# button_controller_v1_0.net
KiCad netlist of a schematic drawn in EAGLE
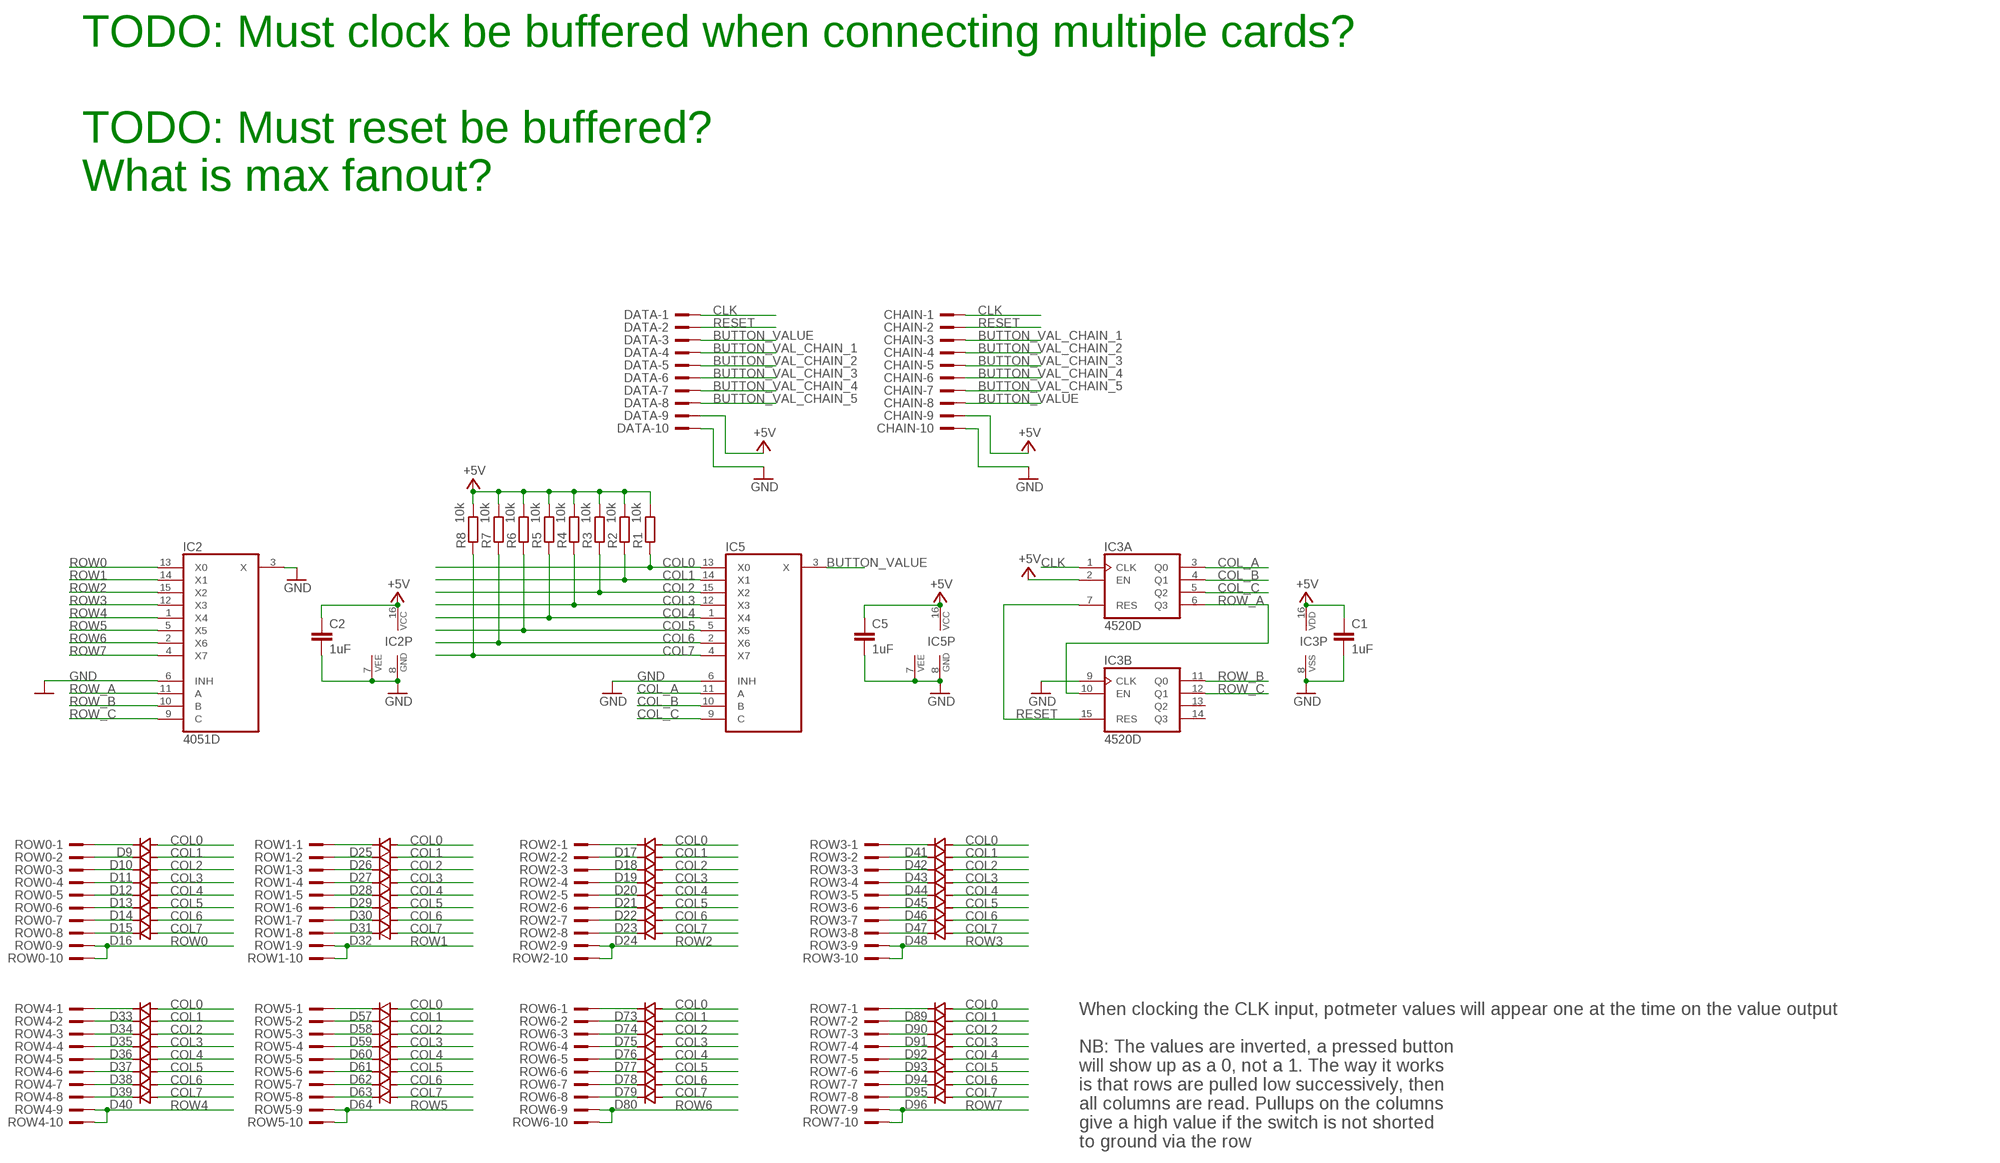
[diagram p0: schematic, sheet 1]

(export (version "E")
  (design (tool "Eeschema 10.0.6"))
  (components
    (comp (ref "C1")
      (value "1uF")
      (footprint "eagle-import:C0603-J")
      (libsource (lib "eagle-import") (part "C-EU-J0603"))
    )
    (comp (ref "C2")
      (value "1uF")
      (footprint "eagle-import:C0603-J")
      (libsource (lib "eagle-import") (part "C-EU-J0603"))
    )
    (comp (ref "C5")
      (value "1uF")
      (footprint "eagle-import:C0603-J")
      (libsource (lib "eagle-import") (part "C-EU-J0603"))
    )
    (comp (ref "CHAIN")
      (value "CONN-IDC-10PS")
      (footprint "eagle-import:CONN-IDC10P-S")
      (libsource (lib "eagle-import") (part "CONN-IDC-10PS"))
    )
    (comp (ref "D9")
      (value "1N4148SOD323")
      (footprint "eagle-import:SOD323J")
      (libsource (lib "eagle-import") (part "1N4148SOD323"))
    )
    (comp (ref "D10")
      (value "1N4148SOD323")
      (footprint "eagle-import:SOD323J")
      (libsource (lib "eagle-import") (part "1N4148SOD323"))
    )
    (comp (ref "D11")
      (value "1N4148SOD323")
      (footprint "eagle-import:SOD323J")
      (libsource (lib "eagle-import") (part "1N4148SOD323"))
    )
    (comp (ref "D12")
      (value "1N4148SOD323")
      (footprint "eagle-import:SOD323J")
      (libsource (lib "eagle-import") (part "1N4148SOD323"))
    )
    (comp (ref "D13")
      (value "1N4148SOD323")
      (footprint "eagle-import:SOD323J")
      (libsource (lib "eagle-import") (part "1N4148SOD323"))
    )
    (comp (ref "D14")
      (value "1N4148SOD323")
      (footprint "eagle-import:SOD323J")
      (libsource (lib "eagle-import") (part "1N4148SOD323"))
    )
    (comp (ref "D15")
      (value "1N4148SOD323")
      (footprint "eagle-import:SOD323J")
      (libsource (lib "eagle-import") (part "1N4148SOD323"))
    )
    (comp (ref "D16")
      (value "1N4148SOD323")
      (footprint "eagle-import:SOD323J")
      (libsource (lib "eagle-import") (part "1N4148SOD323"))
    )
    (comp (ref "D17")
      (value "1N4148SOD323")
      (footprint "eagle-import:SOD323J")
      (libsource (lib "eagle-import") (part "1N4148SOD323"))
    )
    (comp (ref "D18")
      (value "1N4148SOD323")
      (footprint "eagle-import:SOD323J")
      (libsource (lib "eagle-import") (part "1N4148SOD323"))
    )
    (comp (ref "D19")
      (value "1N4148SOD323")
      (footprint "eagle-import:SOD323J")
      (libsource (lib "eagle-import") (part "1N4148SOD323"))
    )
    (comp (ref "D20")
      (value "1N4148SOD323")
      (footprint "eagle-import:SOD323J")
      (libsource (lib "eagle-import") (part "1N4148SOD323"))
    )
    (comp (ref "D21")
      (value "1N4148SOD323")
      (footprint "eagle-import:SOD323J")
      (libsource (lib "eagle-import") (part "1N4148SOD323"))
    )
    (comp (ref "D22")
      (value "1N4148SOD323")
      (footprint "eagle-import:SOD323J")
      (libsource (lib "eagle-import") (part "1N4148SOD323"))
    )
    (comp (ref "D23")
      (value "1N4148SOD323")
      (footprint "eagle-import:SOD323J")
      (libsource (lib "eagle-import") (part "1N4148SOD323"))
    )
    (comp (ref "D24")
      (value "1N4148SOD323")
      (footprint "eagle-import:SOD323J")
      (libsource (lib "eagle-import") (part "1N4148SOD323"))
    )
    (comp (ref "D25")
      (value "1N4148SOD323")
      (footprint "eagle-import:SOD323J")
      (libsource (lib "eagle-import") (part "1N4148SOD323"))
    )
    (comp (ref "D26")
      (value "1N4148SOD323")
      (footprint "eagle-import:SOD323J")
      (libsource (lib "eagle-import") (part "1N4148SOD323"))
    )
    (comp (ref "D27")
      (value "1N4148SOD323")
      (footprint "eagle-import:SOD323J")
      (libsource (lib "eagle-import") (part "1N4148SOD323"))
    )
    (comp (ref "D28")
      (value "1N4148SOD323")
      (footprint "eagle-import:SOD323J")
      (libsource (lib "eagle-import") (part "1N4148SOD323"))
    )
    (comp (ref "D29")
      (value "1N4148SOD323")
      (footprint "eagle-import:SOD323J")
      (libsource (lib "eagle-import") (part "1N4148SOD323"))
    )
    (comp (ref "D30")
      (value "1N4148SOD323")
      (footprint "eagle-import:SOD323J")
      (libsource (lib "eagle-import") (part "1N4148SOD323"))
    )
    (comp (ref "D31")
      (value "1N4148SOD323")
      (footprint "eagle-import:SOD323J")
      (libsource (lib "eagle-import") (part "1N4148SOD323"))
    )
    (comp (ref "D32")
      (value "1N4148SOD323")
      (footprint "eagle-import:SOD323J")
      (libsource (lib "eagle-import") (part "1N4148SOD323"))
    )
    (comp (ref "D33")
      (value "1N4148SOD323")
      (footprint "eagle-import:SOD323J")
      (libsource (lib "eagle-import") (part "1N4148SOD323"))
    )
    (comp (ref "D34")
      (value "1N4148SOD323")
      (footprint "eagle-import:SOD323J")
      (libsource (lib "eagle-import") (part "1N4148SOD323"))
    )
    (comp (ref "D35")
      (value "1N4148SOD323")
      (footprint "eagle-import:SOD323J")
      (libsource (lib "eagle-import") (part "1N4148SOD323"))
    )
    (comp (ref "D36")
      (value "1N4148SOD323")
      (footprint "eagle-import:SOD323J")
      (libsource (lib "eagle-import") (part "1N4148SOD323"))
    )
    (comp (ref "D37")
      (value "1N4148SOD323")
      (footprint "eagle-import:SOD323J")
      (libsource (lib "eagle-import") (part "1N4148SOD323"))
    )
    (comp (ref "D38")
      (value "1N4148SOD323")
      (footprint "eagle-import:SOD323J")
      (libsource (lib "eagle-import") (part "1N4148SOD323"))
    )
    (comp (ref "D39")
      (value "1N4148SOD323")
      (footprint "eagle-import:SOD323J")
      (libsource (lib "eagle-import") (part "1N4148SOD323"))
    )
    (comp (ref "D40")
      (value "1N4148SOD323")
      (footprint "eagle-import:SOD323J")
      (libsource (lib "eagle-import") (part "1N4148SOD323"))
    )
    (comp (ref "D41")
      (value "1N4148SOD323")
      (footprint "eagle-import:SOD323J")
      (libsource (lib "eagle-import") (part "1N4148SOD323"))
    )
    (comp (ref "D42")
      (value "1N4148SOD323")
      (footprint "eagle-import:SOD323J")
      (libsource (lib "eagle-import") (part "1N4148SOD323"))
    )
    (comp (ref "D43")
      (value "1N4148SOD323")
      (footprint "eagle-import:SOD323J")
      (libsource (lib "eagle-import") (part "1N4148SOD323"))
    )
    (comp (ref "D44")
      (value "1N4148SOD323")
      (footprint "eagle-import:SOD323J")
      (libsource (lib "eagle-import") (part "1N4148SOD323"))
    )
    (comp (ref "D45")
      (value "1N4148SOD323")
      (footprint "eagle-import:SOD323J")
      (libsource (lib "eagle-import") (part "1N4148SOD323"))
    )
    (comp (ref "D46")
      (value "1N4148SOD323")
      (footprint "eagle-import:SOD323J")
      (libsource (lib "eagle-import") (part "1N4148SOD323"))
    )
    (comp (ref "D47")
      (value "1N4148SOD323")
      (footprint "eagle-import:SOD323J")
      (libsource (lib "eagle-import") (part "1N4148SOD323"))
    )
    (comp (ref "D48")
      (value "1N4148SOD323")
      (footprint "eagle-import:SOD323J")
      (libsource (lib "eagle-import") (part "1N4148SOD323"))
    )
    (comp (ref "D57")
      (value "1N4148SOD323")
      (footprint "eagle-import:SOD323J")
      (libsource (lib "eagle-import") (part "1N4148SOD323"))
    )
    (comp (ref "D58")
      (value "1N4148SOD323")
      (footprint "eagle-import:SOD323J")
      (libsource (lib "eagle-import") (part "1N4148SOD323"))
    )
    (comp (ref "D59")
      (value "1N4148SOD323")
      (footprint "eagle-import:SOD323J")
      (libsource (lib "eagle-import") (part "1N4148SOD323"))
    )
    (comp (ref "D60")
      (value "1N4148SOD323")
      (footprint "eagle-import:SOD323J")
      (libsource (lib "eagle-import") (part "1N4148SOD323"))
    )
    (comp (ref "D61")
      (value "1N4148SOD323")
      (footprint "eagle-import:SOD323J")
      (libsource (lib "eagle-import") (part "1N4148SOD323"))
    )
    (comp (ref "D62")
      (value "1N4148SOD323")
      (footprint "eagle-import:SOD323J")
      (libsource (lib "eagle-import") (part "1N4148SOD323"))
    )
    (comp (ref "D63")
      (value "1N4148SOD323")
      (footprint "eagle-import:SOD323J")
      (libsource (lib "eagle-import") (part "1N4148SOD323"))
    )
    (comp (ref "D64")
      (value "1N4148SOD323")
      (footprint "eagle-import:SOD323J")
      (libsource (lib "eagle-import") (part "1N4148SOD323"))
    )
    (comp (ref "D73")
      (value "1N4148SOD323")
      (footprint "eagle-import:SOD323J")
      (libsource (lib "eagle-import") (part "1N4148SOD323"))
    )
    (comp (ref "D74")
      (value "1N4148SOD323")
      (footprint "eagle-import:SOD323J")
      (libsource (lib "eagle-import") (part "1N4148SOD323"))
    )
    (comp (ref "D75")
      (value "1N4148SOD323")
      (footprint "eagle-import:SOD323J")
      (libsource (lib "eagle-import") (part "1N4148SOD323"))
    )
    (comp (ref "D76")
      (value "1N4148SOD323")
      (footprint "eagle-import:SOD323J")
      (libsource (lib "eagle-import") (part "1N4148SOD323"))
    )
    (comp (ref "D77")
      (value "1N4148SOD323")
      (footprint "eagle-import:SOD323J")
      (libsource (lib "eagle-import") (part "1N4148SOD323"))
    )
    (comp (ref "D78")
      (value "1N4148SOD323")
      (footprint "eagle-import:SOD323J")
      (libsource (lib "eagle-import") (part "1N4148SOD323"))
    )
    (comp (ref "D79")
      (value "1N4148SOD323")
      (footprint "eagle-import:SOD323J")
      (libsource (lib "eagle-import") (part "1N4148SOD323"))
    )
    (comp (ref "D80")
      (value "1N4148SOD323")
      (footprint "eagle-import:SOD323J")
      (libsource (lib "eagle-import") (part "1N4148SOD323"))
    )
    (comp (ref "D89")
      (value "1N4148SOD323")
      (footprint "eagle-import:SOD323J")
      (libsource (lib "eagle-import") (part "1N4148SOD323"))
    )
    (comp (ref "D90")
      (value "1N4148SOD323")
      (footprint "eagle-import:SOD323J")
      (libsource (lib "eagle-import") (part "1N4148SOD323"))
    )
    (comp (ref "D91")
      (value "1N4148SOD323")
      (footprint "eagle-import:SOD323J")
      (libsource (lib "eagle-import") (part "1N4148SOD323"))
    )
    (comp (ref "D92")
      (value "1N4148SOD323")
      (footprint "eagle-import:SOD323J")
      (libsource (lib "eagle-import") (part "1N4148SOD323"))
    )
    (comp (ref "D93")
      (value "1N4148SOD323")
      (footprint "eagle-import:SOD323J")
      (libsource (lib "eagle-import") (part "1N4148SOD323"))
    )
    (comp (ref "D94")
      (value "1N4148SOD323")
      (footprint "eagle-import:SOD323J")
      (libsource (lib "eagle-import") (part "1N4148SOD323"))
    )
    (comp (ref "D95")
      (value "1N4148SOD323")
      (footprint "eagle-import:SOD323J")
      (libsource (lib "eagle-import") (part "1N4148SOD323"))
    )
    (comp (ref "D96")
      (value "1N4148SOD323")
      (footprint "eagle-import:SOD323J")
      (libsource (lib "eagle-import") (part "1N4148SOD323"))
    )
    (comp (ref "DATA")
      (value "CONN-IDC-10PS")
      (footprint "eagle-import:CONN-IDC10P-S")
      (libsource (lib "eagle-import") (part "CONN-IDC-10PS"))
    )
    (comp (ref "IC2")
      (value "4051D")
      (footprint "eagle-import:SO16")
      (libsource (lib "eagle-import") (part "4051D"))
    )
    (comp (ref "IC3")
      (value "4520D")
      (footprint "eagle-import:SO16")
      (libsource (lib "eagle-import") (part "4520D"))
    )
    (comp (ref "IC5")
      (value "4051D")
      (footprint "eagle-import:SO16")
      (libsource (lib "eagle-import") (part "4051D"))
    )
    (comp (ref "R1")
      (value "10k")
      (footprint "eagle-import:R0603")
      (libsource (lib "eagle-import") (part "R-EU_R0603"))
    )
    (comp (ref "R2")
      (value "10k")
      (footprint "eagle-import:R0603")
      (libsource (lib "eagle-import") (part "R-EU_R0603"))
    )
    (comp (ref "R3")
      (value "10k")
      (footprint "eagle-import:R0603")
      (libsource (lib "eagle-import") (part "R-EU_R0603"))
    )
    (comp (ref "R4")
      (value "10k")
      (footprint "eagle-import:R0603")
      (libsource (lib "eagle-import") (part "R-EU_R0603"))
    )
    (comp (ref "R5")
      (value "10k")
      (footprint "eagle-import:R0603")
      (libsource (lib "eagle-import") (part "R-EU_R0603"))
    )
    (comp (ref "R6")
      (value "10k")
      (footprint "eagle-import:R0603")
      (libsource (lib "eagle-import") (part "R-EU_R0603"))
    )
    (comp (ref "R7")
      (value "10k")
      (footprint "eagle-import:R0603")
      (libsource (lib "eagle-import") (part "R-EU_R0603"))
    )
    (comp (ref "R8")
      (value "10k")
      (footprint "eagle-import:R0603")
      (libsource (lib "eagle-import") (part "R-EU_R0603"))
    )
    (comp (ref "ROW0")
      (value "CONN-IDC-10PS")
      (footprint "eagle-import:CONN-IDC10P-S")
      (libsource (lib "eagle-import") (part "CONN-IDC-10PS"))
    )
    (comp (ref "ROW1")
      (value "CONN-IDC-10PS")
      (footprint "eagle-import:CONN-IDC10P-S")
      (libsource (lib "eagle-import") (part "CONN-IDC-10PS"))
    )
    (comp (ref "ROW2")
      (value "CONN-IDC-10PS")
      (footprint "eagle-import:CONN-IDC10P-S")
      (libsource (lib "eagle-import") (part "CONN-IDC-10PS"))
    )
    (comp (ref "ROW3")
      (value "CONN-IDC-10PS")
      (footprint "eagle-import:CONN-IDC10P-S")
      (libsource (lib "eagle-import") (part "CONN-IDC-10PS"))
    )
    (comp (ref "ROW4")
      (value "CONN-IDC-10PS")
      (footprint "eagle-import:CONN-IDC10P-S")
      (libsource (lib "eagle-import") (part "CONN-IDC-10PS"))
    )
    (comp (ref "ROW5")
      (value "CONN-IDC-10PS")
      (footprint "eagle-import:CONN-IDC10P-S")
      (libsource (lib "eagle-import") (part "CONN-IDC-10PS"))
    )
    (comp (ref "ROW6")
      (value "CONN-IDC-10PS")
      (footprint "eagle-import:CONN-IDC10P-S")
      (libsource (lib "eagle-import") (part "CONN-IDC-10PS"))
    )
    (comp (ref "ROW7")
      (value "CONN-IDC-10PS")
      (footprint "eagle-import:CONN-IDC10P-S")
      (libsource (lib "eagle-import") (part "CONN-IDC-10PS"))
    )
  )
  (nets
    (net (code "1") (name "+5V") (class "Default")
      (node (ref "C1") (pin "1") (pinfunction "1_1") (pintype "passive"))
      (node (ref "C2") (pin "1") (pinfunction "1_1") (pintype "passive"))
      (node (ref "C5") (pin "1") (pinfunction "1_1") (pintype "passive"))
      (node (ref "CHAIN") (pin "9") (pinfunction "KL_9") (pintype "passive"))
      (node (ref "DATA") (pin "9") (pinfunction "KL_9") (pintype "passive"))
      (node (ref "IC2") (pin "16") (pinfunction "VCC_16") (pintype "power_in"))
      (node (ref "IC3") (pin "16") (pinfunction "VDD_16") (pintype "power_in"))
      (node (ref "IC3") (pin "2") (pinfunction "EN_2") (pintype "input"))
      (node (ref "IC5") (pin "16") (pinfunction "VCC_16") (pintype "power_in"))
      (node (ref "R1") (pin "2") (pinfunction "2_2") (pintype "passive"))
      (node (ref "R2") (pin "2") (pinfunction "2_2") (pintype "passive"))
      (node (ref "R3") (pin "2") (pinfunction "2_2") (pintype "passive"))
      (node (ref "R4") (pin "2") (pinfunction "2_2") (pintype "passive"))
      (node (ref "R5") (pin "2") (pinfunction "2_2") (pintype "passive"))
      (node (ref "R6") (pin "2") (pinfunction "2_2") (pintype "passive"))
      (node (ref "R7") (pin "2") (pinfunction "2_2") (pintype "passive"))
      (node (ref "R8") (pin "2") (pinfunction "2_2") (pintype "passive"))
    )
    (net (code "2") (name "/BUTTON_VALUE") (class "Default")
      (node (ref "CHAIN") (pin "8") (pinfunction "KL_8") (pintype "passive"))
      (node (ref "DATA") (pin "3") (pinfunction "KL_3") (pintype "passive"))
      (node (ref "IC5") (pin "3") (pinfunction "X_3") (pintype "bidirectional"))
    )
    (net (code "3") (name "/BUTTON_VAL_CHAIN_1") (class "Default")
      (node (ref "CHAIN") (pin "3") (pinfunction "KL_3") (pintype "passive"))
      (node (ref "DATA") (pin "4") (pinfunction "KL_4") (pintype "passive"))
    )
    (net (code "4") (name "/BUTTON_VAL_CHAIN_2") (class "Default")
      (node (ref "CHAIN") (pin "4") (pinfunction "KL_4") (pintype "passive"))
      (node (ref "DATA") (pin "5") (pinfunction "KL_5") (pintype "passive"))
    )
    (net (code "5") (name "/BUTTON_VAL_CHAIN_3") (class "Default")
      (node (ref "CHAIN") (pin "5") (pinfunction "KL_5") (pintype "passive"))
      (node (ref "DATA") (pin "6") (pinfunction "KL_6") (pintype "passive"))
    )
    (net (code "6") (name "/BUTTON_VAL_CHAIN_4") (class "Default")
      (node (ref "CHAIN") (pin "6") (pinfunction "KL_6") (pintype "passive"))
      (node (ref "DATA") (pin "7") (pinfunction "KL_7") (pintype "passive"))
    )
    (net (code "7") (name "/BUTTON_VAL_CHAIN_5") (class "Default")
      (node (ref "CHAIN") (pin "7") (pinfunction "KL_7") (pintype "passive"))
      (node (ref "DATA") (pin "8") (pinfunction "KL_8") (pintype "passive"))
    )
    (net (code "8") (name "/CLK") (class "Default")
      (node (ref "CHAIN") (pin "1") (pinfunction "KL_1") (pintype "passive"))
      (node (ref "DATA") (pin "1") (pinfunction "KL_1") (pintype "passive"))
      (node (ref "IC3") (pin "1") (pinfunction "CLK_1") (pintype "input"))
    )
    (net (code "9") (name "/COL0") (class "Default")
      (node (ref "D17") (pin "2") (pinfunction "A_2") (pintype "passive"))
      (node (ref "D25") (pin "2") (pinfunction "A_2") (pintype "passive"))
      (node (ref "D33") (pin "2") (pinfunction "A_2") (pintype "passive"))
      (node (ref "D41") (pin "2") (pinfunction "A_2") (pintype "passive"))
      (node (ref "D57") (pin "2") (pinfunction "A_2") (pintype "passive"))
      (node (ref "D73") (pin "2") (pinfunction "A_2") (pintype "passive"))
      (node (ref "D89") (pin "2") (pinfunction "A_2") (pintype "passive"))
      (node (ref "D9") (pin "2") (pinfunction "A_2") (pintype "passive"))
      (node (ref "IC5") (pin "13") (pinfunction "X0_13") (pintype "bidirectional"))
      (node (ref "R1") (pin "1") (pinfunction "1_1") (pintype "passive"))
    )
    (net (code "10") (name "/COL1") (class "Default")
      (node (ref "D10") (pin "2") (pinfunction "A_2") (pintype "passive"))
      (node (ref "D18") (pin "2") (pinfunction "A_2") (pintype "passive"))
      (node (ref "D26") (pin "2") (pinfunction "A_2") (pintype "passive"))
      (node (ref "D34") (pin "2") (pinfunction "A_2") (pintype "passive"))
      (node (ref "D42") (pin "2") (pinfunction "A_2") (pintype "passive"))
      (node (ref "D58") (pin "2") (pinfunction "A_2") (pintype "passive"))
      (node (ref "D74") (pin "2") (pinfunction "A_2") (pintype "passive"))
      (node (ref "D90") (pin "2") (pinfunction "A_2") (pintype "passive"))
      (node (ref "IC5") (pin "14") (pinfunction "X1_14") (pintype "bidirectional"))
      (node (ref "R2") (pin "1") (pinfunction "1_1") (pintype "passive"))
    )
    (net (code "11") (name "/COL2") (class "Default")
      (node (ref "D11") (pin "2") (pinfunction "A_2") (pintype "passive"))
      (node (ref "D19") (pin "2") (pinfunction "A_2") (pintype "passive"))
      (node (ref "D27") (pin "2") (pinfunction "A_2") (pintype "passive"))
      (node (ref "D35") (pin "2") (pinfunction "A_2") (pintype "passive"))
      (node (ref "D43") (pin "2") (pinfunction "A_2") (pintype "passive"))
      (node (ref "D59") (pin "2") (pinfunction "A_2") (pintype "passive"))
      (node (ref "D75") (pin "2") (pinfunction "A_2") (pintype "passive"))
      (node (ref "D91") (pin "2") (pinfunction "A_2") (pintype "passive"))
      (node (ref "IC5") (pin "15") (pinfunction "X2_15") (pintype "bidirectional"))
      (node (ref "R3") (pin "1") (pinfunction "1_1") (pintype "passive"))
    )
    (net (code "12") (name "/COL3") (class "Default")
      (node (ref "D12") (pin "2") (pinfunction "A_2") (pintype "passive"))
      (node (ref "D20") (pin "2") (pinfunction "A_2") (pintype "passive"))
      (node (ref "D28") (pin "2") (pinfunction "A_2") (pintype "passive"))
      (node (ref "D36") (pin "2") (pinfunction "A_2") (pintype "passive"))
      (node (ref "D44") (pin "2") (pinfunction "A_2") (pintype "passive"))
      (node (ref "D60") (pin "2") (pinfunction "A_2") (pintype "passive"))
      (node (ref "D76") (pin "2") (pinfunction "A_2") (pintype "passive"))
      (node (ref "D92") (pin "2") (pinfunction "A_2") (pintype "passive"))
      (node (ref "IC5") (pin "12") (pinfunction "X3_12") (pintype "bidirectional"))
      (node (ref "R4") (pin "1") (pinfunction "1_1") (pintype "passive"))
    )
    (net (code "13") (name "/COL4") (class "Default")
      (node (ref "D13") (pin "2") (pinfunction "A_2") (pintype "passive"))
      (node (ref "D21") (pin "2") (pinfunction "A_2") (pintype "passive"))
      (node (ref "D29") (pin "2") (pinfunction "A_2") (pintype "passive"))
      (node (ref "D37") (pin "2") (pinfunction "A_2") (pintype "passive"))
      (node (ref "D45") (pin "2") (pinfunction "A_2") (pintype "passive"))
      (node (ref "D61") (pin "2") (pinfunction "A_2") (pintype "passive"))
      (node (ref "D77") (pin "2") (pinfunction "A_2") (pintype "passive"))
      (node (ref "D93") (pin "2") (pinfunction "A_2") (pintype "passive"))
      (node (ref "IC5") (pin "1") (pinfunction "X4_1") (pintype "bidirectional"))
      (node (ref "R5") (pin "1") (pinfunction "1_1") (pintype "passive"))
    )
    (net (code "14") (name "/COL5") (class "Default")
      (node (ref "D14") (pin "2") (pinfunction "A_2") (pintype "passive"))
      (node (ref "D22") (pin "2") (pinfunction "A_2") (pintype "passive"))
      (node (ref "D30") (pin "2") (pinfunction "A_2") (pintype "passive"))
      (node (ref "D38") (pin "2") (pinfunction "A_2") (pintype "passive"))
      (node (ref "D46") (pin "2") (pinfunction "A_2") (pintype "passive"))
      (node (ref "D62") (pin "2") (pinfunction "A_2") (pintype "passive"))
      (node (ref "D78") (pin "2") (pinfunction "A_2") (pintype "passive"))
      (node (ref "D94") (pin "2") (pinfunction "A_2") (pintype "passive"))
      (node (ref "IC5") (pin "5") (pinfunction "X5_5") (pintype "bidirectional"))
      (node (ref "R6") (pin "1") (pinfunction "1_1") (pintype "passive"))
    )
    (net (code "15") (name "/COL6") (class "Default")
      (node (ref "D15") (pin "2") (pinfunction "A_2") (pintype "passive"))
      (node (ref "D23") (pin "2") (pinfunction "A_2") (pintype "passive"))
      (node (ref "D31") (pin "2") (pinfunction "A_2") (pintype "passive"))
      (node (ref "D39") (pin "2") (pinfunction "A_2") (pintype "passive"))
      (node (ref "D47") (pin "2") (pinfunction "A_2") (pintype "passive"))
      (node (ref "D63") (pin "2") (pinfunction "A_2") (pintype "passive"))
      (node (ref "D79") (pin "2") (pinfunction "A_2") (pintype "passive"))
      (node (ref "D95") (pin "2") (pinfunction "A_2") (pintype "passive"))
      (node (ref "IC5") (pin "2") (pinfunction "X6_2") (pintype "bidirectional"))
      (node (ref "R7") (pin "1") (pinfunction "1_1") (pintype "passive"))
    )
    (net (code "16") (name "/COL7") (class "Default")
      (node (ref "D16") (pin "2") (pinfunction "A_2") (pintype "passive"))
      (node (ref "D24") (pin "2") (pinfunction "A_2") (pintype "passive"))
      (node (ref "D32") (pin "2") (pinfunction "A_2") (pintype "passive"))
      (node (ref "D40") (pin "2") (pinfunction "A_2") (pintype "passive"))
      (node (ref "D48") (pin "2") (pinfunction "A_2") (pintype "passive"))
      (node (ref "D64") (pin "2") (pinfunction "A_2") (pintype "passive"))
      (node (ref "D80") (pin "2") (pinfunction "A_2") (pintype "passive"))
      (node (ref "D96") (pin "2") (pinfunction "A_2") (pintype "passive"))
      (node (ref "IC5") (pin "4") (pinfunction "X7_4") (pintype "bidirectional"))
      (node (ref "R8") (pin "1") (pinfunction "1_1") (pintype "passive"))
    )
    (net (code "17") (name "/COL_A") (class "Default")
      (node (ref "IC3") (pin "3") (pinfunction "Q0_3") (pintype "output"))
      (node (ref "IC5") (pin "11") (pinfunction "A_11") (pintype "input"))
    )
    (net (code "18") (name "/COL_B") (class "Default")
      (node (ref "IC3") (pin "4") (pinfunction "Q1_4") (pintype "output"))
      (node (ref "IC5") (pin "10") (pinfunction "B_10") (pintype "input"))
    )
    (net (code "19") (name "/COL_C") (class "Default")
      (node (ref "IC3") (pin "5") (pinfunction "Q2_5") (pintype "output"))
      (node (ref "IC5") (pin "9") (pinfunction "C_9") (pintype "input"))
    )
    (net (code "20") (name "/RESET") (class "Default")
      (node (ref "CHAIN") (pin "2") (pinfunction "KL_2") (pintype "passive"))
      (node (ref "DATA") (pin "2") (pinfunction "KL_2") (pintype "passive"))
      (node (ref "IC3") (pin "15") (pinfunction "RES_15") (pintype "input"))
      (node (ref "IC3") (pin "7") (pinfunction "RES_7") (pintype "input"))
    )
    (net (code "21") (name "/ROW0") (class "Default")
      (node (ref "IC2") (pin "13") (pinfunction "X0_13") (pintype "bidirectional"))
      (node (ref "ROW0") (pin "10") (pinfunction "KL_10") (pintype "passive"))
      (node (ref "ROW0") (pin "9") (pinfunction "KL_9") (pintype "passive"))
    )
    (net (code "22") (name "/ROW1") (class "Default")
      (node (ref "IC2") (pin "14") (pinfunction "X1_14") (pintype "bidirectional"))
      (node (ref "ROW1") (pin "10") (pinfunction "KL_10") (pintype "passive"))
      (node (ref "ROW1") (pin "9") (pinfunction "KL_9") (pintype "passive"))
    )
    (net (code "23") (name "/ROW2") (class "Default")
      (node (ref "IC2") (pin "15") (pinfunction "X2_15") (pintype "bidirectional"))
      (node (ref "ROW2") (pin "10") (pinfunction "KL_10") (pintype "passive"))
      (node (ref "ROW2") (pin "9") (pinfunction "KL_9") (pintype "passive"))
    )
    (net (code "24") (name "/ROW3") (class "Default")
      (node (ref "IC2") (pin "12") (pinfunction "X3_12") (pintype "bidirectional"))
      (node (ref "ROW3") (pin "10") (pinfunction "KL_10") (pintype "passive"))
      (node (ref "ROW3") (pin "9") (pinfunction "KL_9") (pintype "passive"))
    )
    (net (code "25") (name "/ROW4") (class "Default")
      (node (ref "IC2") (pin "1") (pinfunction "X4_1") (pintype "bidirectional"))
      (node (ref "ROW4") (pin "10") (pinfunction "KL_10") (pintype "passive"))
      (node (ref "ROW4") (pin "9") (pinfunction "KL_9") (pintype "passive"))
    )
    (net (code "26") (name "/ROW5") (class "Default")
      (node (ref "IC2") (pin "5") (pinfunction "X5_5") (pintype "bidirectional"))
      (node (ref "ROW5") (pin "10") (pinfunction "KL_10") (pintype "passive"))
      (node (ref "ROW5") (pin "9") (pinfunction "KL_9") (pintype "passive"))
    )
    (net (code "27") (name "/ROW6") (class "Default")
      (node (ref "IC2") (pin "2") (pinfunction "X6_2") (pintype "bidirectional"))
      (node (ref "ROW6") (pin "10") (pinfunction "KL_10") (pintype "passive"))
      (node (ref "ROW6") (pin "9") (pinfunction "KL_9") (pintype "passive"))
    )
    (net (code "28") (name "/ROW7") (class "Default")
      (node (ref "IC2") (pin "4") (pinfunction "X7_4") (pintype "bidirectional"))
      (node (ref "ROW7") (pin "10") (pinfunction "KL_10") (pintype "passive"))
      (node (ref "ROW7") (pin "9") (pinfunction "KL_9") (pintype "passive"))
    )
    (net (code "29") (name "/ROW_A") (class "Default")
      (node (ref "IC2") (pin "11") (pinfunction "A_11") (pintype "input"))
      (node (ref "IC3") (pin "10") (pinfunction "EN_10") (pintype "input"))
      (node (ref "IC3") (pin "6") (pinfunction "Q3_6") (pintype "output"))
    )
    (net (code "30") (name "/ROW_B") (class "Default")
      (node (ref "IC2") (pin "10") (pinfunction "B_10") (pintype "input"))
      (node (ref "IC3") (pin "11") (pinfunction "Q0_11") (pintype "output"))
    )
    (net (code "31") (name "/ROW_C") (class "Default")
      (node (ref "IC2") (pin "9") (pinfunction "C_9") (pintype "input"))
      (node (ref "IC3") (pin "12") (pinfunction "Q1_12") (pintype "output"))
    )
    (net (code "32") (name "GND") (class "Default")
      (node (ref "C1") (pin "2") (pinfunction "2_2") (pintype "passive"))
      (node (ref "C2") (pin "2") (pinfunction "2_2") (pintype "passive"))
      (node (ref "C5") (pin "2") (pinfunction "2_2") (pintype "passive"))
      (node (ref "CHAIN") (pin "10") (pinfunction "KL_10") (pintype "passive"))
      (node (ref "DATA") (pin "10") (pinfunction "KL_10") (pintype "passive"))
      (node (ref "IC2") (pin "3") (pinfunction "X_3") (pintype "bidirectional"))
      (node (ref "IC2") (pin "6") (pinfunction "INH_6") (pintype "input"))
      (node (ref "IC2") (pin "7") (pinfunction "VEE_7") (pintype "power_in"))
      (node (ref "IC2") (pin "8") (pinfunction "GND_8") (pintype "power_in"))
      (node (ref "IC3") (pin "8") (pinfunction "VSS_8") (pintype "power_in"))
      (node (ref "IC3") (pin "9") (pinfunction "CLK_9") (pintype "input"))
      (node (ref "IC5") (pin "6") (pinfunction "INH_6") (pintype "input"))
      (node (ref "IC5") (pin "7") (pinfunction "VEE_7") (pintype "power_in"))
      (node (ref "IC5") (pin "8") (pinfunction "GND_8") (pintype "power_in"))
    )
    (net (code "33") (name "Net-(D9-C)") (class "Default")
      (node (ref "D9") (pin "1") (pinfunction "C_1") (pintype "passive"))
      (node (ref "ROW0") (pin "1") (pinfunction "KL_1") (pintype "passive"))
    )
    (net (code "34") (name "Net-(D10-C)") (class "Default")
      (node (ref "D10") (pin "1") (pinfunction "C_1") (pintype "passive"))
      (node (ref "ROW0") (pin "2") (pinfunction "KL_2") (pintype "passive"))
    )
    (net (code "35") (name "Net-(D11-C)") (class "Default")
      (node (ref "D11") (pin "1") (pinfunction "C_1") (pintype "passive"))
      (node (ref "ROW0") (pin "3") (pinfunction "KL_3") (pintype "passive"))
    )
    (net (code "36") (name "Net-(D12-C)") (class "Default")
      (node (ref "D12") (pin "1") (pinfunction "C_1") (pintype "passive"))
      (node (ref "ROW0") (pin "4") (pinfunction "KL_4") (pintype "passive"))
    )
    (net (code "37") (name "Net-(D13-C)") (class "Default")
      (node (ref "D13") (pin "1") (pinfunction "C_1") (pintype "passive"))
      (node (ref "ROW0") (pin "5") (pinfunction "KL_5") (pintype "passive"))
    )
    (net (code "38") (name "Net-(D14-C)") (class "Default")
      (node (ref "D14") (pin "1") (pinfunction "C_1") (pintype "passive"))
      (node (ref "ROW0") (pin "6") (pinfunction "KL_6") (pintype "passive"))
    )
    (net (code "39") (name "Net-(D15-C)") (class "Default")
      (node (ref "D15") (pin "1") (pinfunction "C_1") (pintype "passive"))
      (node (ref "ROW0") (pin "7") (pinfunction "KL_7") (pintype "passive"))
    )
    (net (code "40") (name "Net-(D16-C)") (class "Default")
      (node (ref "D16") (pin "1") (pinfunction "C_1") (pintype "passive"))
      (node (ref "ROW0") (pin "8") (pinfunction "KL_8") (pintype "passive"))
    )
    (net (code "41") (name "Net-(D17-C)") (class "Default")
      (node (ref "D17") (pin "1") (pinfunction "C_1") (pintype "passive"))
      (node (ref "ROW2") (pin "1") (pinfunction "KL_1") (pintype "passive"))
    )
    (net (code "42") (name "Net-(D18-C)") (class "Default")
      (node (ref "D18") (pin "1") (pinfunction "C_1") (pintype "passive"))
      (node (ref "ROW2") (pin "2") (pinfunction "KL_2") (pintype "passive"))
    )
    (net (code "43") (name "Net-(D19-C)") (class "Default")
      (node (ref "D19") (pin "1") (pinfunction "C_1") (pintype "passive"))
      (node (ref "ROW2") (pin "3") (pinfunction "KL_3") (pintype "passive"))
    )
    (net (code "44") (name "Net-(D20-C)") (class "Default")
      (node (ref "D20") (pin "1") (pinfunction "C_1") (pintype "passive"))
      (node (ref "ROW2") (pin "4") (pinfunction "KL_4") (pintype "passive"))
    )
    (net (code "45") (name "Net-(D21-C)") (class "Default")
      (node (ref "D21") (pin "1") (pinfunction "C_1") (pintype "passive"))
      (node (ref "ROW2") (pin "5") (pinfunction "KL_5") (pintype "passive"))
    )
    (net (code "46") (name "Net-(D22-C)") (class "Default")
      (node (ref "D22") (pin "1") (pinfunction "C_1") (pintype "passive"))
      (node (ref "ROW2") (pin "6") (pinfunction "KL_6") (pintype "passive"))
    )
    (net (code "47") (name "Net-(D23-C)") (class "Default")
      (node (ref "D23") (pin "1") (pinfunction "C_1") (pintype "passive"))
      (node (ref "ROW2") (pin "7") (pinfunction "KL_7") (pintype "passive"))
    )
    (net (code "48") (name "Net-(D24-C)") (class "Default")
      (node (ref "D24") (pin "1") (pinfunction "C_1") (pintype "passive"))
      (node (ref "ROW2") (pin "8") (pinfunction "KL_8") (pintype "passive"))
    )
    (net (code "49") (name "Net-(D25-C)") (class "Default")
      (node (ref "D25") (pin "1") (pinfunction "C_1") (pintype "passive"))
      (node (ref "ROW1") (pin "1") (pinfunction "KL_1") (pintype "passive"))
    )
    (net (code "50") (name "Net-(D26-C)") (class "Default")
      (node (ref "D26") (pin "1") (pinfunction "C_1") (pintype "passive"))
      (node (ref "ROW1") (pin "2") (pinfunction "KL_2") (pintype "passive"))
    )
    (net (code "51") (name "Net-(D27-C)") (class "Default")
      (node (ref "D27") (pin "1") (pinfunction "C_1") (pintype "passive"))
      (node (ref "ROW1") (pin "3") (pinfunction "KL_3") (pintype "passive"))
    )
    (net (code "52") (name "Net-(D28-C)") (class "Default")
      (node (ref "D28") (pin "1") (pinfunction "C_1") (pintype "passive"))
      (node (ref "ROW1") (pin "4") (pinfunction "KL_4") (pintype "passive"))
    )
    (net (code "53") (name "Net-(D29-C)") (class "Default")
      (node (ref "D29") (pin "1") (pinfunction "C_1") (pintype "passive"))
      (node (ref "ROW1") (pin "5") (pinfunction "KL_5") (pintype "passive"))
    )
    (net (code "54") (name "Net-(D30-C)") (class "Default")
      (node (ref "D30") (pin "1") (pinfunction "C_1") (pintype "passive"))
      (node (ref "ROW1") (pin "6") (pinfunction "KL_6") (pintype "passive"))
    )
    (net (code "55") (name "Net-(D31-C)") (class "Default")
      (node (ref "D31") (pin "1") (pinfunction "C_1") (pintype "passive"))
      (node (ref "ROW1") (pin "7") (pinfunction "KL_7") (pintype "passive"))
    )
    (net (code "56") (name "Net-(D32-C)") (class "Default")
      (node (ref "D32") (pin "1") (pinfunction "C_1") (pintype "passive"))
      (node (ref "ROW1") (pin "8") (pinfunction "KL_8") (pintype "passive"))
    )
    (net (code "57") (name "Net-(D33-C)") (class "Default")
      (node (ref "D33") (pin "1") (pinfunction "C_1") (pintype "passive"))
      (node (ref "ROW4") (pin "1") (pinfunction "KL_1") (pintype "passive"))
    )
    (net (code "58") (name "Net-(D34-C)") (class "Default")
      (node (ref "D34") (pin "1") (pinfunction "C_1") (pintype "passive"))
      (node (ref "ROW4") (pin "2") (pinfunction "KL_2") (pintype "passive"))
    )
    (net (code "59") (name "Net-(D35-C)") (class "Default")
      (node (ref "D35") (pin "1") (pinfunction "C_1") (pintype "passive"))
      (node (ref "ROW4") (pin "3") (pinfunction "KL_3") (pintype "passive"))
    )
    (net (code "60") (name "Net-(D36-C)") (class "Default")
      (node (ref "D36") (pin "1") (pinfunction "C_1") (pintype "passive"))
      (node (ref "ROW4") (pin "4") (pinfunction "KL_4") (pintype "passive"))
    )
    (net (code "61") (name "Net-(D37-C)") (class "Default")
      (node (ref "D37") (pin "1") (pinfunction "C_1") (pintype "passive"))
      (node (ref "ROW4") (pin "5") (pinfunction "KL_5") (pintype "passive"))
    )
    (net (code "62") (name "Net-(D38-C)") (class "Default")
      (node (ref "D38") (pin "1") (pinfunction "C_1") (pintype "passive"))
      (node (ref "ROW4") (pin "6") (pinfunction "KL_6") (pintype "passive"))
    )
    (net (code "63") (name "Net-(D39-C)") (class "Default")
      (node (ref "D39") (pin "1") (pinfunction "C_1") (pintype "passive"))
      (node (ref "ROW4") (pin "7") (pinfunction "KL_7") (pintype "passive"))
    )
    (net (code "64") (name "Net-(D40-C)") (class "Default")
      (node (ref "D40") (pin "1") (pinfunction "C_1") (pintype "passive"))
      (node (ref "ROW4") (pin "8") (pinfunction "KL_8") (pintype "passive"))
    )
    (net (code "65") (name "Net-(D41-C)") (class "Default")
      (node (ref "D41") (pin "1") (pinfunction "C_1") (pintype "passive"))
      (node (ref "ROW3") (pin "1") (pinfunction "KL_1") (pintype "passive"))
    )
    (net (code "66") (name "Net-(D42-C)") (class "Default")
      (node (ref "D42") (pin "1") (pinfunction "C_1") (pintype "passive"))
      (node (ref "ROW3") (pin "2") (pinfunction "KL_2") (pintype "passive"))
    )
    (net (code "67") (name "Net-(D43-C)") (class "Default")
      (node (ref "D43") (pin "1") (pinfunction "C_1") (pintype "passive"))
      (node (ref "ROW3") (pin "3") (pinfunction "KL_3") (pintype "passive"))
    )
    (net (code "68") (name "Net-(D44-C)") (class "Default")
      (node (ref "D44") (pin "1") (pinfunction "C_1") (pintype "passive"))
      (node (ref "ROW3") (pin "4") (pinfunction "KL_4") (pintype "passive"))
    )
    (net (code "69") (name "Net-(D45-C)") (class "Default")
      (node (ref "D45") (pin "1") (pinfunction "C_1") (pintype "passive"))
      (node (ref "ROW3") (pin "5") (pinfunction "KL_5") (pintype "passive"))
    )
    (net (code "70") (name "Net-(D46-C)") (class "Default")
      (node (ref "D46") (pin "1") (pinfunction "C_1") (pintype "passive"))
      (node (ref "ROW3") (pin "6") (pinfunction "KL_6") (pintype "passive"))
    )
    (net (code "71") (name "Net-(D47-C)") (class "Default")
      (node (ref "D47") (pin "1") (pinfunction "C_1") (pintype "passive"))
      (node (ref "ROW3") (pin "7") (pinfunction "KL_7") (pintype "passive"))
    )
    (net (code "72") (name "Net-(D48-C)") (class "Default")
      (node (ref "D48") (pin "1") (pinfunction "C_1") (pintype "passive"))
      (node (ref "ROW3") (pin "8") (pinfunction "KL_8") (pintype "passive"))
    )
    (net (code "73") (name "Net-(D57-C)") (class "Default")
      (node (ref "D57") (pin "1") (pinfunction "C_1") (pintype "passive"))
      (node (ref "ROW5") (pin "1") (pinfunction "KL_1") (pintype "passive"))
    )
    (net (code "74") (name "Net-(D58-C)") (class "Default")
      (node (ref "D58") (pin "1") (pinfunction "C_1") (pintype "passive"))
      (node (ref "ROW5") (pin "2") (pinfunction "KL_2") (pintype "passive"))
    )
    (net (code "75") (name "Net-(D59-C)") (class "Default")
      (node (ref "D59") (pin "1") (pinfunction "C_1") (pintype "passive"))
      (node (ref "ROW5") (pin "3") (pinfunction "KL_3") (pintype "passive"))
    )
    (net (code "76") (name "Net-(D60-C)") (class "Default")
      (node (ref "D60") (pin "1") (pinfunction "C_1") (pintype "passive"))
      (node (ref "ROW5") (pin "4") (pinfunction "KL_4") (pintype "passive"))
    )
    (net (code "77") (name "Net-(D61-C)") (class "Default")
      (node (ref "D61") (pin "1") (pinfunction "C_1") (pintype "passive"))
      (node (ref "ROW5") (pin "5") (pinfunction "KL_5") (pintype "passive"))
    )
    (net (code "78") (name "Net-(D62-C)") (class "Default")
      (node (ref "D62") (pin "1") (pinfunction "C_1") (pintype "passive"))
      (node (ref "ROW5") (pin "6") (pinfunction "KL_6") (pintype "passive"))
    )
    (net (code "79") (name "Net-(D63-C)") (class "Default")
      (node (ref "D63") (pin "1") (pinfunction "C_1") (pintype "passive"))
      (node (ref "ROW5") (pin "7") (pinfunction "KL_7") (pintype "passive"))
    )
    (net (code "80") (name "Net-(D64-C)") (class "Default")
      (node (ref "D64") (pin "1") (pinfunction "C_1") (pintype "passive"))
      (node (ref "ROW5") (pin "8") (pinfunction "KL_8") (pintype "passive"))
    )
    (net (code "81") (name "Net-(D73-C)") (class "Default")
      (node (ref "D73") (pin "1") (pinfunction "C_1") (pintype "passive"))
      (node (ref "ROW6") (pin "1") (pinfunction "KL_1") (pintype "passive"))
    )
    (net (code "82") (name "Net-(D74-C)") (class "Default")
      (node (ref "D74") (pin "1") (pinfunction "C_1") (pintype "passive"))
      (node (ref "ROW6") (pin "2") (pinfunction "KL_2") (pintype "passive"))
    )
    (net (code "83") (name "Net-(D75-C)") (class "Default")
      (node (ref "D75") (pin "1") (pinfunction "C_1") (pintype "passive"))
      (node (ref "ROW6") (pin "3") (pinfunction "KL_3") (pintype "passive"))
    )
    (net (code "84") (name "Net-(D76-C)") (class "Default")
      (node (ref "D76") (pin "1") (pinfunction "C_1") (pintype "passive"))
      (node (ref "ROW6") (pin "4") (pinfunction "KL_4") (pintype "passive"))
    )
    (net (code "85") (name "Net-(D77-C)") (class "Default")
      (node (ref "D77") (pin "1") (pinfunction "C_1") (pintype "passive"))
      (node (ref "ROW6") (pin "5") (pinfunction "KL_5") (pintype "passive"))
    )
    (net (code "86") (name "Net-(D78-C)") (class "Default")
      (node (ref "D78") (pin "1") (pinfunction "C_1") (pintype "passive"))
      (node (ref "ROW6") (pin "6") (pinfunction "KL_6") (pintype "passive"))
    )
    (net (code "87") (name "Net-(D79-C)") (class "Default")
      (node (ref "D79") (pin "1") (pinfunction "C_1") (pintype "passive"))
      (node (ref "ROW6") (pin "7") (pinfunction "KL_7") (pintype "passive"))
    )
    (net (code "88") (name "Net-(D80-C)") (class "Default")
      (node (ref "D80") (pin "1") (pinfunction "C_1") (pintype "passive"))
      (node (ref "ROW6") (pin "8") (pinfunction "KL_8") (pintype "passive"))
    )
    (net (code "89") (name "Net-(D89-C)") (class "Default")
      (node (ref "D89") (pin "1") (pinfunction "C_1") (pintype "passive"))
      (node (ref "ROW7") (pin "1") (pinfunction "KL_1") (pintype "passive"))
    )
    (net (code "90") (name "Net-(D90-C)") (class "Default")
      (node (ref "D90") (pin "1") (pinfunction "C_1") (pintype "passive"))
      (node (ref "ROW7") (pin "2") (pinfunction "KL_2") (pintype "passive"))
    )
    (net (code "91") (name "Net-(D91-C)") (class "Default")
      (node (ref "D91") (pin "1") (pinfunction "C_1") (pintype "passive"))
      (node (ref "ROW7") (pin "3") (pinfunction "KL_3") (pintype "passive"))
    )
    (net (code "92") (name "Net-(D92-C)") (class "Default")
      (node (ref "D92") (pin "1") (pinfunction "C_1") (pintype "passive"))
      (node (ref "ROW7") (pin "4") (pinfunction "KL_4") (pintype "passive"))
    )
    (net (code "93") (name "Net-(D93-C)") (class "Default")
      (node (ref "D93") (pin "1") (pinfunction "C_1") (pintype "passive"))
      (node (ref "ROW7") (pin "5") (pinfunction "KL_5") (pintype "passive"))
    )
    (net (code "94") (name "Net-(D94-C)") (class "Default")
      (node (ref "D94") (pin "1") (pinfunction "C_1") (pintype "passive"))
      (node (ref "ROW7") (pin "6") (pinfunction "KL_6") (pintype "passive"))
    )
    (net (code "95") (name "Net-(D95-C)") (class "Default")
      (node (ref "D95") (pin "1") (pinfunction "C_1") (pintype "passive"))
      (node (ref "ROW7") (pin "7") (pinfunction "KL_7") (pintype "passive"))
    )
    (net (code "96") (name "Net-(D96-C)") (class "Default")
      (node (ref "D96") (pin "1") (pinfunction "C_1") (pintype "passive"))
      (node (ref "ROW7") (pin "8") (pinfunction "KL_8") (pintype "passive"))
    )
    (net (code "97") (name "unconnected-(IC3B-Q2-Pad13)") (class "Default")
      (node (ref "IC3") (pin "13") (pinfunction "Q2_13") (pintype "output"))
    )
    (net (code "98") (name "unconnected-(IC3B-Q3-Pad14)") (class "Default")
      (node (ref "IC3") (pin "14") (pinfunction "Q3_14") (pintype "output"))
    )
  )
)
